# 07-STM32WL3-TX.net
KiCad netlist of a schematic drawn in Altium Designer
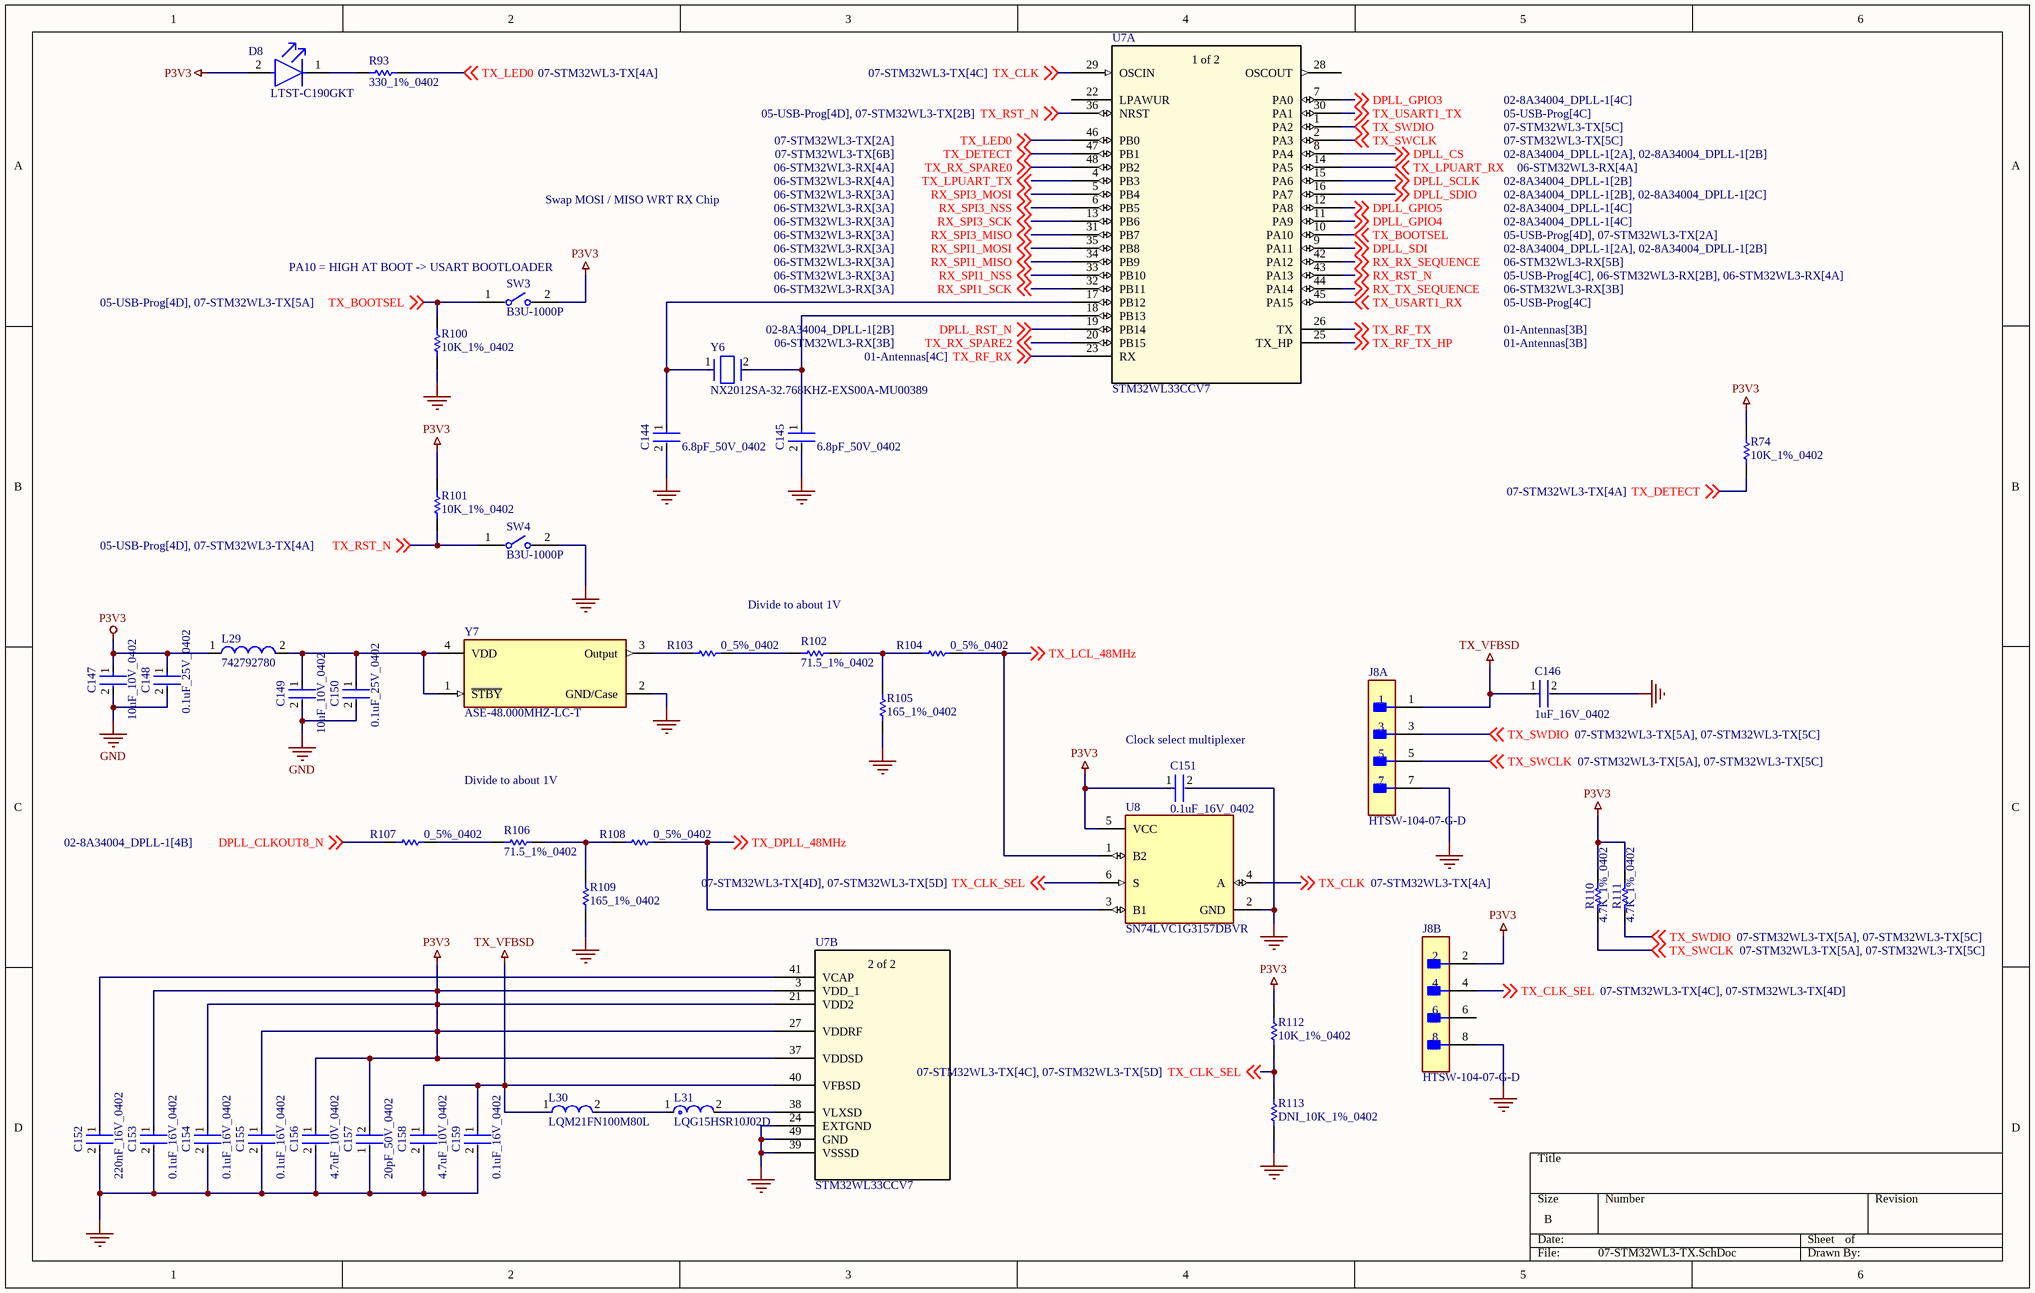
[diagram p0: 07-STM32WL3-TX.SchDoc]

(export (version "E")
  (design (tool "Eeschema 10.0.6"))
  (components
    (comp (ref "C144")
      (value "6.8pF_50V_0402")
      (footprint "FP-GJM155-0_05-IPC_A")
      (description "Multi-Layer Ceramic Capacitor 6.8pF C0G  ±0.25pF 0402 Paper T/R")
      (fields (field (name "VOLTAGE") "50V"))
      (libsource (lib "Altium Content Vault") (part "02cd4be3c70576c341d710602a673aa"))
    )
    (comp (ref "C145")
      (value "6.8pF_50V_0402")
      (footprint "FP-GJM155-0_05-IPC_A")
      (description "Multi-Layer Ceramic Capacitor 6.8pF C0G  ±0.25pF 0402 Paper T/R")
      (fields (field (name "VOLTAGE") "50V"))
      (libsource (lib "Altium Content Vault") (part "02cd4be3c70576c341d710602a673aa"))
    )
    (comp (ref "C146")
      (value "1uF_16V_0402")
      (footprint "FP-0402-L_1_0_0_05-W_0_5-IPC_A")
      (description "None")
      (fields (field (name "TOLERANCE") "10%"))
      (libsource (lib "Altium Content Vault") (part "b4654b650e69147ec39a6b967a45e02"))
    )
    (comp (ref "C147")
      (value "10uF_10V_0402")
      (footprint "FP-CL05A106MP5NUNC-MFG")
      (description "CAP CER 10UF 10V X5R 0402")
      (fields
        (field (name "OCTOPART") "https://octopart.com/cl05a106mp5nunc-samsung-22457395")
        (field (name "TOLERANCE") "20%")
      )
      (libsource (lib "Altium Content Vault") (part "b4654b650e69147ec39a6b967a45e02"))
    )
    (comp (ref "C148")
      (value "0.1uF_25V_0402")
      (footprint "FP-0402-L_1_0_1-W_0_5_0_1-IPC_C")
      (description "General Purpose Ceramic Capacitor, 0402, 100nF, 10%, X7R, 15%, 25V")
      (fields (field (name "VOLTAGE") "25V") (field (name "TOLERANCE") "10%"))
      (libsource (lib "Altium Content Vault") (part "b4654b650e69147ec39a6b967a45e02"))
    )
    (comp (ref "C149")
      (value "10uF_10V_0402")
      (footprint "FP-CL05A106MP5NUNC-MFG")
      (description "CAP CER 10UF 10V X5R 0402")
      (fields
        (field (name "OCTOPART") "https://octopart.com/cl05a106mp5nunc-samsung-22457395")
        (field (name "TOLERANCE") "20%")
      )
      (libsource (lib "Altium Content Vault") (part "b4654b650e69147ec39a6b967a45e02"))
    )
    (comp (ref "C150")
      (value "0.1uF_25V_0402")
      (footprint "FP-0402-L_1_0_1-W_0_5_0_1-IPC_C")
      (description "General Purpose Ceramic Capacitor, 0402, 100nF, 10%, X7R, 15%, 25V")
      (fields (field (name "VOLTAGE") "25V") (field (name "TOLERANCE") "10%"))
      (libsource (lib "Altium Content Vault") (part "b4654b650e69147ec39a6b967a45e02"))
    )
    (comp (ref "C151")
      (value "0.1uF_16V_0402")
      (footprint "FP-C0402-BB-MFG")
      (description "CAP CER 0.1UF 16V 5% X7R 0402")
      (fields
        (field (name "MANUFACTURER") "Kemet")
        (field (name "MANUFACTURER PART NUMBER") "C0402C104J4RACTU")
      )
      (libsource (lib "Altium Content Vault") (part "b4654b650e69147ec39a6b967a45e02"))
    )
    (comp (ref "C152")
      (value "220nF_16V_0402")
      (footprint "FP-GRM155-0_05-IPC_C")
      (description "Chip Multilayer Ceramic Capacitors for General Purpose, 0402, 0.22uF, X7R, 15%, 10%, 16V")
      (fields (field (name "VOLTAGE") "16V") (field (name "TOLERANCE") "10%"))
      (libsource (lib "Altium Content Vault") (part "02cd4be3c70576c341d710602a673aa"))
    )
    (comp (ref "C153")
      (value "0.1uF_16V_0402")
      (footprint "FP-C0402-BB-MFG")
      (description "CAP CER 0.1UF 16V 5% X7R 0402")
      (fields
        (field (name "MANUFACTURER") "Kemet")
        (field (name "MANUFACTURER PART NUMBER") "C0402C104J4RACTU")
      )
      (libsource (lib "Altium Content Vault") (part "b4654b650e69147ec39a6b967a45e02"))
    )
    (comp (ref "C154")
      (value "0.1uF_16V_0402")
      (footprint "FP-C0402-BB-MFG")
      (description "CAP CER 0.1UF 16V 5% X7R 0402")
      (fields
        (field (name "MANUFACTURER") "Kemet")
        (field (name "MANUFACTURER PART NUMBER") "C0402C104J4RACTU")
      )
      (libsource (lib "Altium Content Vault") (part "b4654b650e69147ec39a6b967a45e02"))
    )
    (comp (ref "C155")
      (value "0.1uF_16V_0402")
      (footprint "FP-C0402-BB-MFG")
      (description "CAP CER 0.1UF 16V 5% X7R 0402")
      (fields
        (field (name "MANUFACTURER") "Kemet")
        (field (name "MANUFACTURER PART NUMBER") "C0402C104J4RACTU")
      )
      (libsource (lib "Altium Content Vault") (part "b4654b650e69147ec39a6b967a45e02"))
    )
    (comp (ref "C156")
      (value "4.7uF_10V_0402")
      (footprint "FP-C1005-050-0_15-MFG")
      (description "CAP CER 4.7UF 10V X5R 0402")
      (fields (field (name "TOLERANCE") "10%"))
      (libsource (lib "Altium Content Vault") (part "b4654b650e69147ec39a6b967a45e02"))
    )
    (comp (ref "C157")
      (value "20pF_50V_0402")
      (footprint "FP-CBR04C-MFG")
      (description "CAP CER 20PF 50V C0G/NP0 0402")
      (fields
        (field (name "MANUFACTURER") "KEMET")
        (field (name "OCTOPART") "https://octopart.com/cbr04c200j5gac-kemet-20446742")
      )
      (libsource (lib "Altium Content Vault") (part "236180d848d6139a670b325ea6854c9"))
    )
    (comp (ref "C158")
      (value "4.7uF_10V_0402")
      (footprint "FP-C1005-050-0_15-MFG")
      (description "CAP CER 4.7UF 10V X5R 0402")
      (fields (field (name "TOLERANCE") "10%"))
      (libsource (lib "Altium Content Vault") (part "b4654b650e69147ec39a6b967a45e02"))
    )
    (comp (ref "C159")
      (value "0.1uF_16V_0402")
      (footprint "FP-C0402-BB-MFG")
      (description "CAP CER 0.1UF 16V 5% X7R 0402")
      (fields
        (field (name "MANUFACTURER") "Kemet")
        (field (name "MANUFACTURER PART NUMBER") "C0402C104J4RACTU")
      )
      (libsource (lib "Altium Content Vault") (part "b4654b650e69147ec39a6b967a45e02"))
    )
    (comp (ref "D8")
      (value "LTST-C190GKT")
      (footprint "FP-LTST-C190GKT-MFG")
      (description "LED GREEN CLEAR CHIP SMD")
      (fields (field (name "VOLTAGE") "2V"))
      (libsource (lib "Altium Content Vault") (part "8706943c75ba83719d021d2fdc84c58"))
    )
    (comp (ref "J8")
      (value "HTSW-104-07-G-D")
      (footprint "FP-HTSW-104-07-G-D-MFG")
      (description "CONN HEADER VERT 8POS 2.54MM")
      (fields
        (field (name "MANUFACTURER") "Samtec")
        (field (name "OCTOPART") "https://octopart.com/htsw-104-07-g-d-samtec-10613822")
      )
      (libsource (lib "Altium Content Vault") (part "811e954b9c034aa737de4d9295cbe7e"))
    )
    (comp (ref "L29")
      (value "742792780")
      (footprint "SMD-0402")
      (description "SMD EMI Suppression Ferrite Bead WE-CBF, Z = 220 Ohm")
      (libsource (lib "Altium Content Vault") (part "PAS-IND-INDUCTOR-2"))
    )
    (comp (ref "L30")
      (value "LQM21FN100M80L")
      (footprint "FP-LQM21DH_70-IPC_C")
      (description "Multilayer Type Inductor for Power Lines, 0805 (2012), 10μH, 20%, 0.39Ω, 100mA")
      (fields (field (name "TOLERANCE") "20%"))
      (libsource (lib "Altium Content Vault") (part "725321dda6339637d4d059423bc1c3c"))
    )
    (comp (ref "L31")
      (value "LQG15HSR10J02D")
      (footprint "FP-LQG15HH_02-IPC_A")
      (description "Multilayer type RF Inductor 100nH ±5% 1.25Ω 200mA 0402")
      (fields (field (name "TOLERANCE") "5%"))
      (libsource (lib "Altium Content Vault") (part "4cc4b267dca4c8e51f7102f422741d8"))
    )
    (comp (ref "R74")
      (value "10K_1%_0402")
      (footprint "RESC1005X40X25NL10T10")
      (fields (field (name "MANUFACTURER") "Bourns") (field (name "PART NUMBER") "CR0402-FX-1002GLF"))
      (libsource (lib "Altium Content Vault") (part "RES"))
    )
    (comp (ref "R93")
      (value "330_1%_0402")
      (footprint "RESC1005X40X25NL10T10")
      (fields (field (name "MANUFACTURER") "Panasonic") (field (name "PART NUMBER") "ERA-2AED331X"))
      (libsource (lib "Altium Content Vault") (part "RES"))
    )
    (comp (ref "R100")
      (value "10K_1%_0402")
      (footprint "RESC1005X40X25NL10T10")
      (fields (field (name "MANUFACTURER") "Bourns") (field (name "PART NUMBER") "CR0402-FX-1002GLF"))
      (libsource (lib "Altium Content Vault") (part "RES"))
    )
    (comp (ref "R101")
      (value "10K_1%_0402")
      (footprint "RESC1005X40X25NL10T10")
      (fields (field (name "MANUFACTURER") "Bourns") (field (name "PART NUMBER") "CR0402-FX-1002GLF"))
      (libsource (lib "Altium Content Vault") (part "RES"))
    )
    (comp (ref "R102")
      (value "71.5_1%_0402")
      (footprint "RESC1005X40X25NL05T05")
      (fields (field (name "MANUFACTURER") "Vishay Dale") (field (name "PART NUMBER") "CRCW040271R5FKED"))
      (libsource (lib "Altium Content Vault") (part "RES"))
    )
    (comp (ref "R103")
      (value "0_5%_0402")
      (footprint "RESC1005X40X25NL05T10")
      (fields (field (name "MANUFACTURER") "Panasonic") (field (name "PART NUMBER") "ERJ-U020R00X"))
      (libsource (lib "Altium Content Vault") (part "RES"))
    )
    (comp (ref "R104")
      (value "0_5%_0402")
      (footprint "RESC1005X40X25NL05T10")
      (fields (field (name "MANUFACTURER") "Panasonic") (field (name "PART NUMBER") "ERJ-U020R00X"))
      (libsource (lib "Altium Content Vault") (part "RES"))
    )
    (comp (ref "R105")
      (value "165_1%_0402")
      (footprint "RESC1005X40X25NL05T05")
      (fields (field (name "MANUFACTURER") "Vishay Dale") (field (name "PART NUMBER") "CRCW0402165RFKED"))
      (libsource (lib "Altium Content Vault") (part "RES"))
    )
    (comp (ref "R106")
      (value "71.5_1%_0402")
      (footprint "RESC1005X40X25NL05T05")
      (fields (field (name "MANUFACTURER") "Vishay Dale") (field (name "PART NUMBER") "CRCW040271R5FKED"))
      (libsource (lib "Altium Content Vault") (part "RES"))
    )
    (comp (ref "R107")
      (value "0_5%_0402")
      (footprint "RESC1005X40X25NL05T10")
      (fields (field (name "MANUFACTURER") "Panasonic") (field (name "PART NUMBER") "ERJ-U020R00X"))
      (libsource (lib "Altium Content Vault") (part "RES"))
    )
    (comp (ref "R108")
      (value "0_5%_0402")
      (footprint "RESC1005X40X25NL05T10")
      (fields (field (name "MANUFACTURER") "Panasonic") (field (name "PART NUMBER") "ERJ-U020R00X"))
      (libsource (lib "Altium Content Vault") (part "RES"))
    )
    (comp (ref "R109")
      (value "165_1%_0402")
      (footprint "RESC1005X40X25NL05T05")
      (fields (field (name "MANUFACTURER") "Vishay Dale") (field (name "PART NUMBER") "CRCW0402165RFKED"))
      (libsource (lib "Altium Content Vault") (part "RES"))
    )
    (comp (ref "R110")
      (value "4.7K_1%_0402")
      (footprint "RESC1005X40X25NL10T10")
      (fields (field (name "MANUFACTURER") "Bourns") (field (name "PART NUMBER") "CR0402-FX-4701GLF"))
      (libsource (lib "Altium Content Vault") (part "RES"))
    )
    (comp (ref "R111")
      (value "4.7K_1%_0402")
      (footprint "RESC1005X40X25NL10T10")
      (fields (field (name "MANUFACTURER") "Bourns") (field (name "PART NUMBER") "CR0402-FX-4701GLF"))
      (libsource (lib "Altium Content Vault") (part "RES"))
    )
    (comp (ref "R112")
      (value "10K_1%_0402")
      (footprint "RESC1005X40X25NL10T10")
      (fields (field (name "MANUFACTURER") "Bourns") (field (name "PART NUMBER") "CR0402-FX-1002GLF"))
      (libsource (lib "Altium Content Vault") (part "RES"))
    )
    (comp (ref "R113")
      (value "DNI_10K_1%_0402")
      (footprint "RESC1005X40X25NL10T10")
      (fields (field (name "MANUFACTURER") "Bourns") (field (name "PART NUMBER") "CR0402-FX-1002GLF"))
      (libsource (lib "Altium Content Vault") (part "RES"))
    )
    (comp (ref "SW3")
      (value "B3U-1000P")
      (footprint "FP-B3U-1000P-MFG")
      (description "SWITCH TACTILE SPST-NO 0.05A 12V")
      (libsource (lib "Altium Content Vault") (part "ae622034201233ca1abcedc05908f33"))
    )
    (comp (ref "SW4")
      (value "B3U-1000P")
      (footprint "FP-B3U-1000P-MFG")
      (description "SWITCH TACTILE SPST-NO 0.05A 12V")
      (libsource (lib "Altium Content Vault") (part "ae622034201233ca1abcedc05908f33"))
    )
    (comp (ref "U7")
      (value "STM32WL33CCV7")
      (footprint "UFQFPN-48_STM")
      (description "No Description Available")
      (libsource (lib "STM32WL33CCV7") (part "STM32WL33CCV7"))
    )
    (comp (ref "U8")
      (value "SN74LVC1G3157DBVR")
      (footprint "FP-DBV0006A-IPC_C")
      (description "IC SWITCH SPDT SOT23-6")
      (libsource (lib "Altium Content Vault") (part "14cfcf06f1431fbc89496e2a44d6624"))
    )
    (comp (ref "Y6")
      (value "NX2012SA-32.768KHZ-EXS00A-MU00389")
      (footprint "FP-NX2012SA-MFG")
      (description "CRYSTAL 32.768KHZ 7PF SMD")
      (fields
        (field (name "MANUFACTURER") "NDK America")
        (field (name "OCTOPART") "https://octopart.com/nx2012sa-32.768khz-exs00a-mu00389-ndk-92010294")
      )
      (libsource (lib "Altium Content Vault") (part "c23a69dc6c9e2f18f2079038eb95dd1"))
    )
    (comp (ref "Y7")
      (value "ASE-48.000MHZ-LC-T")
      (footprint "FP-ASE-MFG")
      (description "XTAL Oscillator 48MHz ±50ppm CMOS 3.3V 4-SMD 3.2mm x 2.5mm")
      (libsource (lib "Altium Content Vault") (part "61a724e6190563596ac712fef61ad37"))
    )
  )
  (nets
    (net (code "1") (name "DPLL_CLKOUT8_N") (class "Default")
      (node (ref "R107") (pin "1") (pinfunction "1_1") (pintype "passive"))
    )
    (net (code "2") (name "DPLL_CS") (class "Default")
      (node (ref "U7") (pin "8") (pinfunction "PA4_8") (pintype "bidirectional"))
    )
    (net (code "3") (name "DPLL_GPIO3") (class "Default")
      (node (ref "U7") (pin "7") (pinfunction "PA0_7") (pintype "bidirectional"))
    )
    (net (code "4") (name "DPLL_GPIO4") (class "Default")
      (node (ref "U7") (pin "11") (pinfunction "PA9_11") (pintype "bidirectional"))
    )
    (net (code "5") (name "DPLL_GPIO5") (class "Default")
      (node (ref "U7") (pin "12") (pinfunction "PA8_12") (pintype "bidirectional"))
    )
    (net (code "6") (name "DPLL_RST_N") (class "Default")
      (node (ref "U7") (pin "19") (pinfunction "PB14_19") (pintype "bidirectional"))
    )
    (net (code "7") (name "DPLL_SCLK") (class "Default")
      (node (ref "U7") (pin "15") (pinfunction "PA6_15") (pintype "bidirectional"))
    )
    (net (code "8") (name "DPLL_SDI") (class "Default")
      (node (ref "U7") (pin "9") (pinfunction "PA11_9") (pintype "bidirectional"))
    )
    (net (code "9") (name "DPLL_SDIO") (class "Default")
      (node (ref "U7") (pin "16") (pinfunction "PA7_16") (pintype "bidirectional"))
    )
    (net (code "10") (name "GND") (class "Default")
      (node (ref "C144") (pin "2") (pinfunction "2_2") (pintype "passive"))
      (node (ref "C145") (pin "2") (pinfunction "2_2") (pintype "passive"))
      (node (ref "C146") (pin "2") (pinfunction "2_2") (pintype "passive"))
      (node (ref "C147") (pin "2") (pinfunction "2_2") (pintype "passive"))
      (node (ref "C148") (pin "2") (pinfunction "2_2") (pintype "passive"))
      (node (ref "C149") (pin "2") (pinfunction "2_2") (pintype "passive"))
      (node (ref "C150") (pin "2") (pinfunction "2_2") (pintype "passive"))
      (node (ref "C151") (pin "2") (pinfunction "2_2") (pintype "passive"))
      (node (ref "C152") (pin "2") (pinfunction "2_2") (pintype "passive"))
      (node (ref "C153") (pin "2") (pinfunction "2_2") (pintype "passive"))
      (node (ref "C154") (pin "2") (pinfunction "2_2") (pintype "passive"))
      (node (ref "C155") (pin "2") (pinfunction "2_2") (pintype "passive"))
      (node (ref "C156") (pin "2") (pinfunction "2_2") (pintype "passive"))
      (node (ref "C157") (pin "1") (pinfunction "1_1") (pintype "passive"))
      (node (ref "C158") (pin "2") (pinfunction "2_2") (pintype "passive"))
      (node (ref "C159") (pin "2") (pinfunction "2_2") (pintype "passive"))
      (node (ref "J8") (pin "7") (pinfunction "7_7") (pintype "passive"))
      (node (ref "J8") (pin "8") (pinfunction "8_8") (pintype "passive"))
      (node (ref "R100") (pin "2") (pinfunction "2_2") (pintype "passive"))
      (node (ref "R105") (pin "1") (pinfunction "1_1") (pintype "passive"))
      (node (ref "R109") (pin "1") (pinfunction "1_1") (pintype "passive"))
      (node (ref "R113") (pin "2") (pinfunction "2_2") (pintype "passive"))
      (node (ref "SW4") (pin "2") (pinfunction "2_2") (pintype "passive"))
      (node (ref "U7") (pin "24") (pinfunction "EXTGND_24") (pintype "power_in"))
      (node (ref "U7") (pin "39") (pinfunction "VSSSD_39") (pintype "power_in"))
      (node (ref "U7") (pin "49") (pinfunction "GND_49") (pintype "power_in"))
      (node (ref "U8") (pin "2") (pinfunction "GND_2") (pintype "power_in"))
      (node (ref "Y7") (pin "2") (pinfunction "GND/Case_2") (pintype "power_in"))
    )
    (net (code "11") (name "Net-(D8-C)") (class "Default")
      (node (ref "D8") (pin "1") (pinfunction "C_1") (pintype "passive"))
      (node (ref "R93") (pin "2") (pinfunction "2_2") (pintype "passive"))
    )
    (net (code "12") (name "Net-(L30-Pad2)") (class "Default")
      (node (ref "L30") (pin "2") (pinfunction "2_2") (pintype "passive"))
      (node (ref "L31") (pin "1") (pinfunction "1_1") (pintype "passive"))
    )
    (net (code "13") (name "Net-(R102-Pad1)") (class "Default")
      (node (ref "R102") (pin "1") (pinfunction "1_1") (pintype "passive"))
      (node (ref "R103") (pin "2") (pinfunction "2_2") (pintype "passive"))
    )
    (net (code "14") (name "Net-(R102-Pad2)") (class "Default")
      (node (ref "R102") (pin "2") (pinfunction "2_2") (pintype "passive"))
      (node (ref "R104") (pin "1") (pinfunction "1_1") (pintype "passive"))
      (node (ref "R105") (pin "2") (pinfunction "2_2") (pintype "passive"))
    )
    (net (code "15") (name "Net-(R106-Pad1)") (class "Default")
      (node (ref "R106") (pin "1") (pinfunction "1_1") (pintype "passive"))
      (node (ref "R107") (pin "2") (pinfunction "2_2") (pintype "passive"))
    )
    (net (code "16") (name "Net-(R106-Pad2)") (class "Default")
      (node (ref "R106") (pin "2") (pinfunction "2_2") (pintype "passive"))
      (node (ref "R108") (pin "1") (pinfunction "1_1") (pintype "passive"))
      (node (ref "R109") (pin "2") (pinfunction "2_2") (pintype "passive"))
    )
    (net (code "17") (name "Net-(U7A-PB12)") (class "Default")
      (node (ref "C144") (pin "1") (pinfunction "1_1") (pintype "passive"))
      (node (ref "U7") (pin "17") (pinfunction "PB12_17") (pintype "bidirectional"))
      (node (ref "Y6") (pin "1") (pinfunction "1_1") (pintype "passive"))
    )
    (net (code "18") (name "Net-(U7A-PB13)") (class "Default")
      (node (ref "C145") (pin "1") (pinfunction "1_1") (pintype "passive"))
      (node (ref "U7") (pin "18") (pinfunction "PB13_18") (pintype "bidirectional"))
      (node (ref "Y6") (pin "2") (pinfunction "2_2") (pintype "passive"))
    )
    (net (code "19") (name "Net-(U7B-VCAP)") (class "Default")
      (node (ref "C152") (pin "1") (pinfunction "1_1") (pintype "passive"))
      (node (ref "U7") (pin "41") (pinfunction "VCAP_41") (pintype "power_in"))
    )
    (net (code "20") (name "Net-(U7B-VLXSD)") (class "Default")
      (node (ref "L31") (pin "2") (pinfunction "2_2") (pintype "passive"))
      (node (ref "U7") (pin "38") (pinfunction "VLXSD_38") (pintype "power_in"))
    )
    (net (code "21") (name "Net-(Y7-Output)") (class "Default")
      (node (ref "R103") (pin "1") (pinfunction "1_1") (pintype "passive"))
      (node (ref "Y7") (pin "3") (pinfunction "Output_3") (pintype "output"))
    )
    (net (code "22") (name "Net-(Y7-VDD)") (class "Default")
      (node (ref "C149") (pin "1") (pinfunction "1_1") (pintype "passive"))
      (node (ref "C150") (pin "1") (pinfunction "1_1") (pintype "passive"))
      (node (ref "L29") (pin "2") (pinfunction "2_2") (pintype "passive"))
      (node (ref "Y7") (pin "1") (pinfunction "~{STBY}_1") (pintype "input"))
      (node (ref "Y7") (pin "4") (pinfunction "VDD_4") (pintype "power_in"))
    )
    (net (code "23") (name "P3V3") (class "Default")
      (node (ref "C147") (pin "1") (pinfunction "1_1") (pintype "passive"))
      (node (ref "C148") (pin "1") (pinfunction "1_1") (pintype "passive"))
      (node (ref "C151") (pin "1") (pinfunction "1_1") (pintype "passive"))
      (node (ref "C153") (pin "1") (pinfunction "1_1") (pintype "passive"))
      (node (ref "C154") (pin "1") (pinfunction "1_1") (pintype "passive"))
      (node (ref "C155") (pin "1") (pinfunction "1_1") (pintype "passive"))
      (node (ref "C156") (pin "1") (pinfunction "1_1") (pintype "passive"))
      (node (ref "C157") (pin "2") (pinfunction "2_2") (pintype "passive"))
      (node (ref "D8") (pin "2") (pinfunction "A_2") (pintype "passive"))
      (node (ref "J8") (pin "2") (pinfunction "2_2") (pintype "passive"))
      (node (ref "L29") (pin "1") (pinfunction "1_1") (pintype "passive"))
      (node (ref "R101") (pin "1") (pinfunction "1_1") (pintype "passive"))
      (node (ref "R110") (pin "2") (pinfunction "2_2") (pintype "passive"))
      (node (ref "R111") (pin "2") (pinfunction "2_2") (pintype "passive"))
      (node (ref "R112") (pin "1") (pinfunction "1_1") (pintype "passive"))
      (node (ref "R74") (pin "1") (pinfunction "1_1") (pintype "passive"))
      (node (ref "SW3") (pin "2") (pinfunction "2_2") (pintype "passive"))
      (node (ref "U7") (pin "21") (pinfunction "VDD2_21") (pintype "power_in"))
      (node (ref "U7") (pin "27") (pinfunction "VDDRF_27") (pintype "power_in"))
      (node (ref "U7") (pin "3") (pinfunction "VDD_1_3") (pintype "power_in"))
      (node (ref "U7") (pin "37") (pinfunction "VDDSD_37") (pintype "power_in"))
      (node (ref "U8") (pin "5") (pinfunction "VCC_5") (pintype "power_in"))
    )
    (net (code "24") (name "RX_RST_N") (class "Default")
      (node (ref "U7") (pin "43") (pinfunction "PA13_43") (pintype "bidirectional"))
    )
    (net (code "25") (name "RX_RX_SEQUENCE") (class "Default")
      (node (ref "U7") (pin "42") (pinfunction "PA12_42") (pintype "bidirectional"))
    )
    (net (code "26") (name "RX_SPI1_MISO") (class "Default")
      (node (ref "U7") (pin "34") (pinfunction "PB9_34") (pintype "bidirectional"))
    )
    (net (code "27") (name "RX_SPI1_MOSI") (class "Default")
      (node (ref "U7") (pin "35") (pinfunction "PB8_35") (pintype "bidirectional"))
    )
    (net (code "28") (name "RX_SPI1_NSS") (class "Default")
      (node (ref "U7") (pin "33") (pinfunction "PB10_33") (pintype "bidirectional"))
    )
    (net (code "29") (name "RX_SPI1_SCK") (class "Default")
      (node (ref "U7") (pin "32") (pinfunction "PB11_32") (pintype "bidirectional"))
    )
    (net (code "30") (name "RX_SPI3_MISO") (class "Default")
      (node (ref "U7") (pin "31") (pinfunction "PB7_31") (pintype "bidirectional"))
    )
    (net (code "31") (name "RX_SPI3_MOSI") (class "Default")
      (node (ref "U7") (pin "5") (pinfunction "PB4_5") (pintype "bidirectional"))
    )
    (net (code "32") (name "RX_SPI3_NSS") (class "Default")
      (node (ref "U7") (pin "6") (pinfunction "PB5_6") (pintype "bidirectional"))
    )
    (net (code "33") (name "RX_SPI3_SCK") (class "Default")
      (node (ref "U7") (pin "13") (pinfunction "PB6_13") (pintype "bidirectional"))
    )
    (net (code "34") (name "RX_TX_SEQUENCE") (class "Default")
      (node (ref "U7") (pin "44") (pinfunction "PA14_44") (pintype "bidirectional"))
    )
    (net (code "35") (name "TX_BOOTSEL") (class "Default")
      (node (ref "R100") (pin "1") (pinfunction "1_1") (pintype "passive"))
      (node (ref "SW3") (pin "1") (pinfunction "1_1") (pintype "passive"))
      (node (ref "U7") (pin "10") (pinfunction "PA10_10") (pintype "bidirectional"))
    )
    (net (code "36") (name "TX_CLK") (class "Default")
      (node (ref "U7") (pin "29") (pinfunction "OSCIN_29") (pintype "input"))
      (node (ref "U8") (pin "4") (pinfunction "A_4") (pintype "bidirectional"))
    )
    (net (code "37") (name "TX_CLK_SEL") (class "Default")
      (node (ref "J8") (pin "4") (pinfunction "4_4") (pintype "passive"))
      (node (ref "R112") (pin "2") (pinfunction "2_2") (pintype "passive"))
      (node (ref "R113") (pin "1") (pinfunction "1_1") (pintype "passive"))
      (node (ref "U8") (pin "6") (pinfunction "S_6") (pintype "input"))
    )
    (net (code "38") (name "TX_DETECT") (class "Default")
      (node (ref "R74") (pin "2") (pinfunction "2_2") (pintype "passive"))
      (node (ref "U7") (pin "47") (pinfunction "PB1_47") (pintype "bidirectional"))
    )
    (net (code "39") (name "TX_DPLL_48MHz") (class "Default")
      (node (ref "R108") (pin "2") (pinfunction "2_2") (pintype "passive"))
      (node (ref "U8") (pin "3") (pinfunction "B1_3") (pintype "bidirectional"))
    )
    (net (code "40") (name "TX_LCL_48MHz") (class "Default")
      (node (ref "R104") (pin "2") (pinfunction "2_2") (pintype "passive"))
      (node (ref "U8") (pin "1") (pinfunction "B2_1") (pintype "bidirectional"))
    )
    (net (code "41") (name "TX_LED0") (class "Default")
      (node (ref "R93") (pin "1") (pinfunction "1_1") (pintype "passive"))
      (node (ref "U7") (pin "46") (pinfunction "PB0_46") (pintype "bidirectional"))
    )
    (net (code "42") (name "TX_LPUART_RX") (class "Default")
      (node (ref "U7") (pin "14") (pinfunction "PA5_14") (pintype "bidirectional"))
    )
    (net (code "43") (name "TX_LPUART_TX") (class "Default")
      (node (ref "U7") (pin "4") (pinfunction "PB3_4") (pintype "bidirectional"))
    )
    (net (code "44") (name "TX_RF_RX") (class "Default")
      (node (ref "U7") (pin "23") (pinfunction "RX_23") (pintype "passive"))
    )
    (net (code "45") (name "TX_RF_TX") (class "Default")
      (node (ref "U7") (pin "26") (pinfunction "TX_26") (pintype "passive"))
    )
    (net (code "46") (name "TX_RF_TX_HP") (class "Default")
      (node (ref "U7") (pin "25") (pinfunction "TX_HP_25") (pintype "passive"))
    )
    (net (code "47") (name "TX_RST_N") (class "Default")
      (node (ref "R101") (pin "2") (pinfunction "2_2") (pintype "passive"))
      (node (ref "SW4") (pin "1") (pinfunction "1_1") (pintype "passive"))
      (node (ref "U7") (pin "36") (pinfunction "NRST_36") (pintype "bidirectional"))
    )
    (net (code "48") (name "TX_RX_SPARE0") (class "Default")
      (node (ref "U7") (pin "48") (pinfunction "PB2_48") (pintype "bidirectional"))
    )
    (net (code "49") (name "TX_RX_SPARE2") (class "Default")
      (node (ref "U7") (pin "20") (pinfunction "PB15_20") (pintype "bidirectional"))
    )
    (net (code "50") (name "TX_SWCLK") (class "Default")
      (node (ref "J8") (pin "5") (pinfunction "5_5") (pintype "passive"))
      (node (ref "R110") (pin "1") (pinfunction "1_1") (pintype "passive"))
      (node (ref "U7") (pin "2") (pinfunction "PA3_2") (pintype "bidirectional"))
    )
    (net (code "51") (name "TX_SWDIO") (class "Default")
      (node (ref "J8") (pin "3") (pinfunction "3_3") (pintype "passive"))
      (node (ref "R111") (pin "1") (pinfunction "1_1") (pintype "passive"))
      (node (ref "U7") (pin "1") (pinfunction "PA2_1") (pintype "bidirectional"))
    )
    (net (code "52") (name "TX_USART1_RX") (class "Default")
      (node (ref "U7") (pin "45") (pinfunction "PA15_45") (pintype "bidirectional"))
    )
    (net (code "53") (name "TX_USART1_TX") (class "Default")
      (node (ref "U7") (pin "30") (pinfunction "PA1_30") (pintype "bidirectional"))
    )
    (net (code "54") (name "TX_VFBSD") (class "Default")
      (node (ref "C146") (pin "1") (pinfunction "1_1") (pintype "passive"))
      (node (ref "C158") (pin "1") (pinfunction "1_1") (pintype "passive"))
      (node (ref "C159") (pin "1") (pinfunction "1_1") (pintype "passive"))
      (node (ref "J8") (pin "1") (pinfunction "1_1") (pintype "passive"))
      (node (ref "L30") (pin "1") (pinfunction "1_1") (pintype "passive"))
      (node (ref "U7") (pin "40") (pinfunction "VFBSD_40") (pintype "power_in"))
    )
    (net (code "55") (name "unconnected-(J8-Pad6)") (class "Default")
      (node (ref "J8") (pin "6") (pinfunction "6_6") (pintype "passive"))
    )
    (net (code "56") (name "unconnected-(U7A-LPAWUR-Pad22)") (class "Default")
      (node (ref "U7") (pin "22") (pinfunction "LPAWUR_22") (pintype "passive"))
    )
    (net (code "57") (name "unconnected-(U7A-OSCOUT-Pad28)") (class "Default")
      (node (ref "U7") (pin "28") (pinfunction "OSCOUT_28") (pintype "output"))
    )
  )
)
